# TeleInfoNode.net
KiCad netlist of a schematic drawn in EAGLE
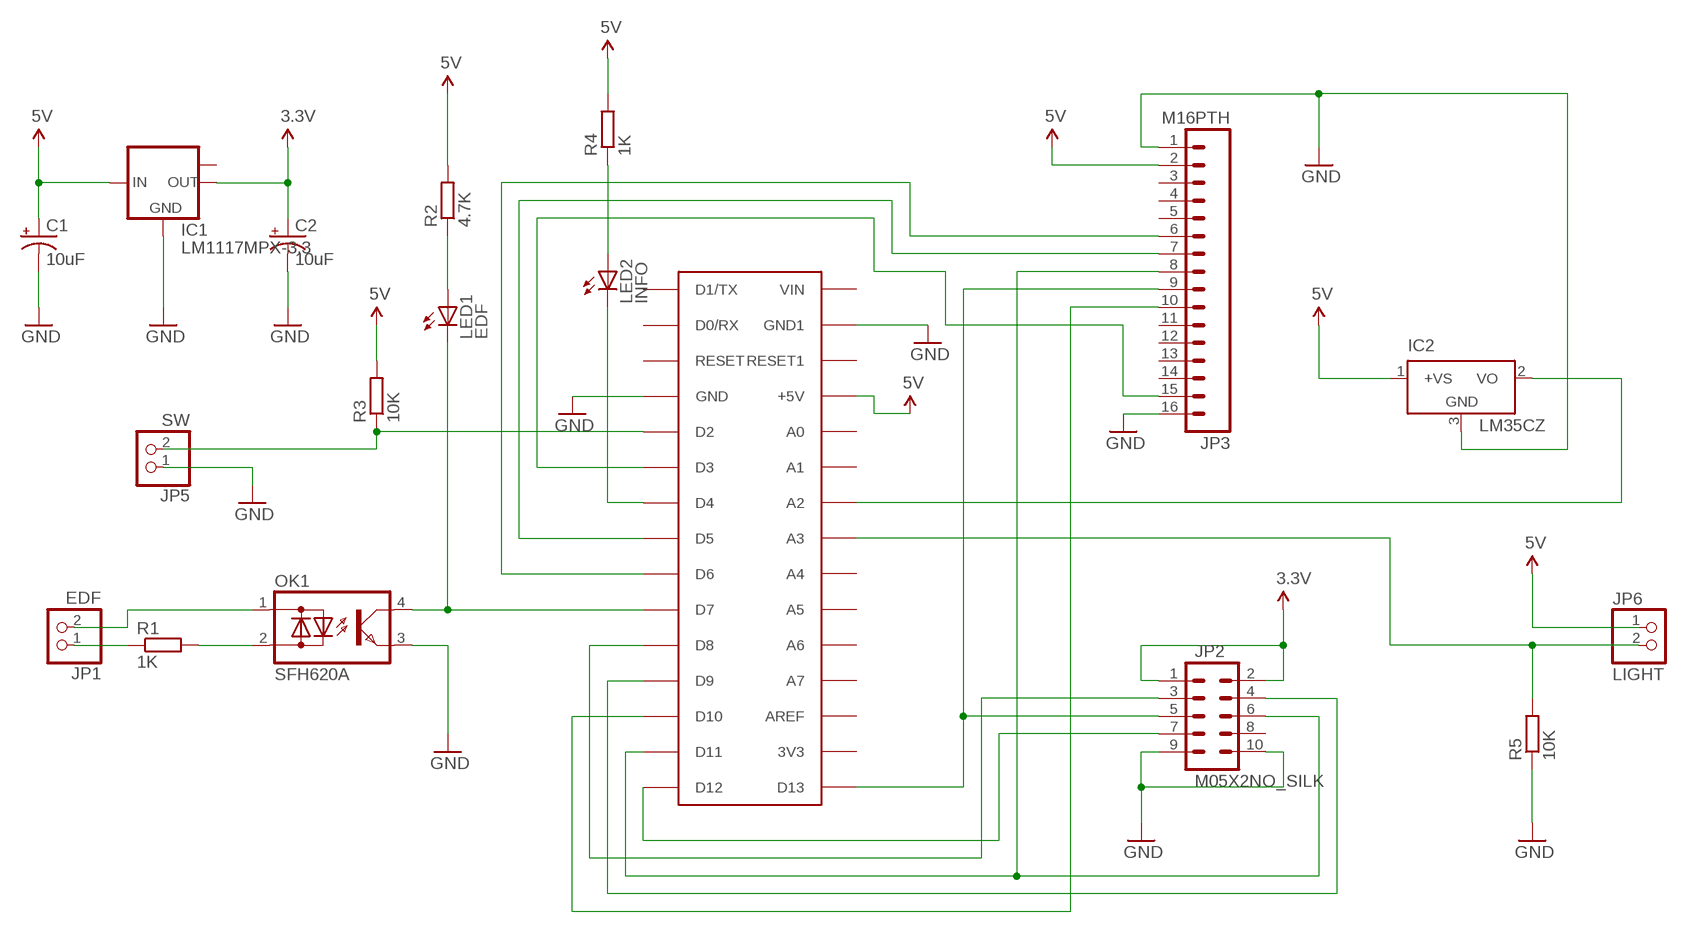
[diagram p0: schematic, sheet 1]

(export (version "E")
  (design (tool "Eeschema 10.0.6"))
  (components
    (comp (ref "C1")
      (value "10uF")
      (footprint "eagle-import:EIA3216")
      (libsource (lib "eagle-import") (part "10UF-16V-10%(TANT)"))
    )
    (comp (ref "C2")
      (value "10uF")
      (footprint "eagle-import:EIA3216")
      (libsource (lib "eagle-import") (part "10UF-16V-10%(TANT)"))
    )
    (comp (ref "IC1")
      (value "LM1117MPX-3.3")
      (footprint "eagle-import:SOT223")
      (libsource (lib "eagle-import") (part "LM1117MPX-3.3"))
    )
    (comp (ref "IC2")
      (value "LM35CZ")
      (footprint "eagle-import:TO92")
      (libsource (lib "eagle-import") (part "LM35CZ"))
    )
    (comp (ref "JP1")
      (value "EDF")
      (footprint "eagle-import:1X02")
      (libsource (lib "eagle-import") (part "PINHD-1X2"))
    )
    (comp (ref "JP2")
      (value "M05X2NO_SILK")
      (footprint "eagle-import:2X5_NOSILK")
      (libsource (lib "eagle-import") (part "M05X2NO_SILK"))
    )
    (comp (ref "JP3")
      (value "M16PTH")
      (footprint "eagle-import:1X16")
      (libsource (lib "eagle-import") (part "M16PTH"))
    )
    (comp (ref "JP5")
      (value "SW")
      (footprint "eagle-import:1X02")
      (libsource (lib "eagle-import") (part "PINHD-1X2"))
    )
    (comp (ref "JP6")
      (value "LIGHT")
      (footprint "eagle-import:1X02")
      (libsource (lib "eagle-import") (part "PINHD-1X2"))
    )
    (comp (ref "LED1")
      (value "EDF")
      (footprint "eagle-import:LED3MM")
      (libsource (lib "eagle-import") (part "LED3MM"))
    )
    (comp (ref "LED2")
      (value "INFO")
      (footprint "eagle-import:LED3MM")
      (libsource (lib "eagle-import") (part "LED3MM"))
    )
    (comp (ref "OK1")
      (value "SFH620A")
      (footprint "eagle-import:DIL04")
      (fields (field (name "MPN") "SFH620A-2"))
      (libsource (lib "eagle-import") (part "SFH620A"))
    )
    (comp (ref "R1")
      (value "1K")
      (footprint "eagle-import:0204_7")
      (libsource (lib "eagle-import") (part "R-EU_0204/7"))
    )
    (comp (ref "R2")
      (value "4.7K")
      (footprint "eagle-import:0204_7")
      (libsource (lib "eagle-import") (part "R-EU_0204/7"))
    )
    (comp (ref "R3")
      (value "10K")
      (footprint "eagle-import:0204_7")
      (libsource (lib "eagle-import") (part "R-EU_0204/7"))
    )
    (comp (ref "R4")
      (value "1K")
      (footprint "eagle-import:0204_7")
      (libsource (lib "eagle-import") (part "R-EU_0204/7"))
    )
    (comp (ref "R5")
      (value "10K")
      (footprint "eagle-import:0204_7")
      (libsource (lib "eagle-import") (part "R-EU_0204/7"))
    )
    (comp (ref "U$1")
      (value "ARDUINONANO")
      (footprint "eagle-import:PDIP-32")
      (libsource (lib "eagle-import") (part "ARDUINONANO"))
    )
  )
  (nets
    (net (code "1") (name "3.3V") (class "Default")
      (node (ref "C2") (pin "A") (pinfunction "+_A") (pintype "passive"))
      (node (ref "IC1") (pin "2") (pinfunction "OUT_2") (pintype "passive"))
      (node (ref "JP2") (pin "1") (pinfunction "1_1") (pintype "passive"))
      (node (ref "JP2") (pin "2") (pinfunction "2_2") (pintype "passive"))
    )
    (net (code "2") (name "5V") (class "Default")
      (node (ref "C1") (pin "A") (pinfunction "+_A") (pintype "passive"))
      (node (ref "IC1") (pin "3") (pinfunction "IN_3") (pintype "input"))
      (node (ref "IC2") (pin "1") (pinfunction "+VS_1") (pintype "input"))
      (node (ref "JP3") (pin "2") (pinfunction "2_2") (pintype "passive"))
      (node (ref "JP6") (pin "1") (pinfunction "1_1") (pintype "passive"))
      (node (ref "R2") (pin "2") (pinfunction "2_2") (pintype "passive"))
      (node (ref "R3") (pin "2") (pinfunction "2_2") (pintype "passive"))
      (node (ref "R4") (pin "2") (pinfunction "2_2") (pintype "passive"))
      (node (ref "U$1") (pin "+5V") (pinfunction "+5V_+5V") (pintype "bidirectional"))
    )
    (net (code "3") (name "GND") (class "Default")
      (node (ref "C1") (pin "C") (pinfunction "-_C") (pintype "passive"))
      (node (ref "C2") (pin "C") (pinfunction "-_C") (pintype "passive"))
      (node (ref "IC1") (pin "1") (pinfunction "GND_1") (pintype "input"))
      (node (ref "IC2") (pin "3") (pinfunction "GND_3") (pintype "power_in"))
      (node (ref "JP2") (pin "10") (pinfunction "10_10") (pintype "passive"))
      (node (ref "JP2") (pin "9") (pinfunction "9_9") (pintype "passive"))
      (node (ref "JP3") (pin "1") (pinfunction "1_1") (pintype "passive"))
      (node (ref "JP3") (pin "16") (pinfunction "16_16") (pintype "passive"))
      (node (ref "JP5") (pin "1") (pinfunction "1_1") (pintype "passive"))
      (node (ref "OK1") (pin "3") (pinfunction "E_3") (pintype "passive"))
      (node (ref "R5") (pin "1") (pinfunction "1_1") (pintype "passive"))
      (node (ref "U$1") (pin "GND") (pinfunction "GND_GND") (pintype "bidirectional"))
      (node (ref "U$1") (pin "GND1") (pinfunction "GND1_GND1") (pintype "bidirectional"))
    )
    (net (code "4") (name "Net-(IC2-VO)") (class "Default")
      (node (ref "IC2") (pin "2") (pinfunction "VO_2") (pintype "input"))
      (node (ref "U$1") (pin "A2") (pinfunction "A2_A2") (pintype "bidirectional"))
    )
    (net (code "5") (name "Net-(JP1-Pad1)") (class "Default")
      (node (ref "JP1") (pin "1") (pinfunction "1_1") (pintype "passive"))
      (node (ref "R1") (pin "1") (pinfunction "1_1") (pintype "passive"))
    )
    (net (code "6") (name "Net-(JP2-Pad3)") (class "Default")
      (node (ref "JP2") (pin "3") (pinfunction "3_3") (pintype "passive"))
      (node (ref "U$1") (pin "D8") (pinfunction "D8_D8") (pintype "bidirectional"))
    )
    (net (code "7") (name "Net-(JP2-Pad4)") (class "Default")
      (node (ref "JP2") (pin "4") (pinfunction "4_4") (pintype "passive"))
      (node (ref "U$1") (pin "D9") (pinfunction "D9_D9") (pintype "bidirectional"))
    )
    (net (code "8") (name "Net-(JP2-Pad5)") (class "Default")
      (node (ref "JP2") (pin "5") (pinfunction "5_5") (pintype "passive"))
      (node (ref "JP3") (pin "9") (pinfunction "9_9") (pintype "passive"))
      (node (ref "U$1") (pin "D13") (pinfunction "D13_D13") (pintype "bidirectional"))
    )
    (net (code "9") (name "Net-(JP2-Pad6)") (class "Default")
      (node (ref "JP2") (pin "6") (pinfunction "6_6") (pintype "passive"))
      (node (ref "JP3") (pin "8") (pinfunction "8_8") (pintype "passive"))
      (node (ref "U$1") (pin "D11") (pinfunction "D11_D11") (pintype "bidirectional"))
    )
    (net (code "10") (name "Net-(JP2-Pad7)") (class "Default")
      (node (ref "JP2") (pin "7") (pinfunction "7_7") (pintype "passive"))
      (node (ref "U$1") (pin "D12") (pinfunction "D12_D12") (pintype "bidirectional"))
    )
    (net (code "11") (name "Net-(JP3-Pad6)") (class "Default")
      (node (ref "JP3") (pin "6") (pinfunction "6_6") (pintype "passive"))
      (node (ref "U$1") (pin "D6") (pinfunction "D6_D6") (pintype "bidirectional"))
    )
    (net (code "12") (name "Net-(JP3-Pad7)") (class "Default")
      (node (ref "JP3") (pin "7") (pinfunction "7_7") (pintype "passive"))
      (node (ref "U$1") (pin "D5") (pinfunction "D5_D5") (pintype "bidirectional"))
    )
    (net (code "13") (name "Net-(JP3-Pad10)") (class "Default")
      (node (ref "JP3") (pin "10") (pinfunction "10_10") (pintype "passive"))
      (node (ref "U$1") (pin "D10") (pinfunction "D10_D10") (pintype "bidirectional"))
    )
    (net (code "14") (name "Net-(JP3-Pad15)") (class "Default")
      (node (ref "JP3") (pin "15") (pinfunction "15_15") (pintype "passive"))
      (node (ref "U$1") (pin "D3") (pinfunction "D3_D3") (pintype "bidirectional"))
    )
    (net (code "15") (name "Net-(JP5-Pad2)") (class "Default")
      (node (ref "JP5") (pin "2") (pinfunction "2_2") (pintype "passive"))
      (node (ref "R3") (pin "1") (pinfunction "1_1") (pintype "passive"))
      (node (ref "U$1") (pin "D2") (pinfunction "D2_D2") (pintype "bidirectional"))
    )
    (net (code "16") (name "Net-(JP6-Pad2)") (class "Default")
      (node (ref "JP6") (pin "2") (pinfunction "2_2") (pintype "passive"))
      (node (ref "R5") (pin "2") (pinfunction "2_2") (pintype "passive"))
      (node (ref "U$1") (pin "A3") (pinfunction "A3_A3") (pintype "bidirectional"))
    )
    (net (code "17") (name "Net-(LED1-C)") (class "Default")
      (node (ref "LED1") (pin "K") (pinfunction "C_K") (pintype "passive"))
      (node (ref "OK1") (pin "4") (pinfunction "C_4") (pintype "passive"))
      (node (ref "U$1") (pin "D7") (pinfunction "D7_D7") (pintype "bidirectional"))
    )
    (net (code "18") (name "Net-(LED1-PadA)") (class "Default")
      (node (ref "LED1") (pin "A") (pinfunction "A_A") (pintype "passive"))
      (node (ref "R2") (pin "1") (pinfunction "1_1") (pintype "passive"))
    )
    (net (code "19") (name "Net-(LED2-C)") (class "Default")
      (node (ref "LED2") (pin "K") (pinfunction "C_K") (pintype "passive"))
      (node (ref "U$1") (pin "D4") (pinfunction "D4_D4") (pintype "bidirectional"))
    )
    (net (code "20") (name "Net-(LED2-PadA)") (class "Default")
      (node (ref "LED2") (pin "A") (pinfunction "A_A") (pintype "passive"))
      (node (ref "R4") (pin "1") (pinfunction "1_1") (pintype "passive"))
    )
    (net (code "21") (name "Net-(OK1-AC1)") (class "Default")
      (node (ref "JP1") (pin "2") (pinfunction "2_2") (pintype "passive"))
      (node (ref "OK1") (pin "1") (pinfunction "AC1_1") (pintype "passive"))
    )
    (net (code "22") (name "Net-(OK1-AC2)") (class "Default")
      (node (ref "OK1") (pin "2") (pinfunction "AC2_2") (pintype "passive"))
      (node (ref "R1") (pin "2") (pinfunction "2_2") (pintype "passive"))
    )
    (net (code "23") (name "unconnected-(IC1-OUT1-PadTAB)") (class "Default")
      (node (ref "IC1") (pin "TAB") (pinfunction "OUT1_TAB") (pintype "passive"))
    )
    (net (code "24") (name "unconnected-(JP2-Pad8)") (class "Default")
      (node (ref "JP2") (pin "8") (pinfunction "8_8") (pintype "passive"))
    )
    (net (code "25") (name "unconnected-(JP3-Pad3)") (class "Default")
      (node (ref "JP3") (pin "3") (pinfunction "3_3") (pintype "passive"))
    )
    (net (code "26") (name "unconnected-(JP3-Pad4)") (class "Default")
      (node (ref "JP3") (pin "4") (pinfunction "4_4") (pintype "passive"))
    )
    (net (code "27") (name "unconnected-(JP3-Pad5)") (class "Default")
      (node (ref "JP3") (pin "5") (pinfunction "5_5") (pintype "passive"))
    )
    (net (code "28") (name "unconnected-(JP3-Pad11)") (class "Default")
      (node (ref "JP3") (pin "11") (pinfunction "11_11") (pintype "passive"))
    )
    (net (code "29") (name "unconnected-(JP3-Pad12)") (class "Default")
      (node (ref "JP3") (pin "12") (pinfunction "12_12") (pintype "passive"))
    )
    (net (code "30") (name "unconnected-(JP3-Pad13)") (class "Default")
      (node (ref "JP3") (pin "13") (pinfunction "13_13") (pintype "passive"))
    )
    (net (code "31") (name "unconnected-(JP3-Pad14)") (class "Default")
      (node (ref "JP3") (pin "14") (pinfunction "14_14") (pintype "passive"))
    )
    (net (code "32") (name "unconnected-(U$1-Pad3V3)") (class "Default")
      (node (ref "U$1") (pin "3V3") (pinfunction "3V3_3V3") (pintype "bidirectional"))
    )
    (net (code "33") (name "unconnected-(U$1-PadA0)") (class "Default")
      (node (ref "U$1") (pin "A0") (pinfunction "A0_A0") (pintype "bidirectional"))
    )
    (net (code "34") (name "unconnected-(U$1-PadA1)") (class "Default")
      (node (ref "U$1") (pin "A1") (pinfunction "A1_A1") (pintype "bidirectional"))
    )
    (net (code "35") (name "unconnected-(U$1-PadA4)") (class "Default")
      (node (ref "U$1") (pin "A4") (pinfunction "A4_A4") (pintype "bidirectional"))
    )
    (net (code "36") (name "unconnected-(U$1-PadA5)") (class "Default")
      (node (ref "U$1") (pin "A5") (pinfunction "A5_A5") (pintype "bidirectional"))
    )
    (net (code "37") (name "unconnected-(U$1-PadA6)") (class "Default")
      (node (ref "U$1") (pin "A6") (pinfunction "A6_A6") (pintype "bidirectional"))
    )
    (net (code "38") (name "unconnected-(U$1-PadA7)") (class "Default")
      (node (ref "U$1") (pin "A7") (pinfunction "A7_A7") (pintype "bidirectional"))
    )
    (net (code "39") (name "unconnected-(U$1-PadAREF)") (class "Default")
      (node (ref "U$1") (pin "AREF") (pinfunction "AREF_AREF") (pintype "bidirectional"))
    )
    (net (code "40") (name "unconnected-(U$1-PadD0{slash}RX)") (class "Default")
      (node (ref "U$1") (pin "D0/RX") (pinfunction "D0/RX_D0/RX") (pintype "bidirectional"))
    )
    (net (code "41") (name "unconnected-(U$1-PadD1{slash}TX)") (class "Default")
      (node (ref "U$1") (pin "D1/TX") (pinfunction "D1/TX_D1/TX") (pintype "bidirectional"))
    )
    (net (code "42") (name "unconnected-(U$1-PadRESET)") (class "Default")
      (node (ref "U$1") (pin "RESET") (pinfunction "RESET_RESET") (pintype "bidirectional"))
    )
    (net (code "43") (name "unconnected-(U$1-PadRESET1)") (class "Default")
      (node (ref "U$1") (pin "RESET1") (pinfunction "RESET1_RESET1") (pintype "bidirectional"))
    )
    (net (code "44") (name "unconnected-(U$1-PadVIN)") (class "Default")
      (node (ref "U$1") (pin "VIN") (pinfunction "VIN_VIN") (pintype "bidirectional"))
    )
  )
)
